# Fake6523.net
KiCad netlist of a schematic drawn in EAGLE
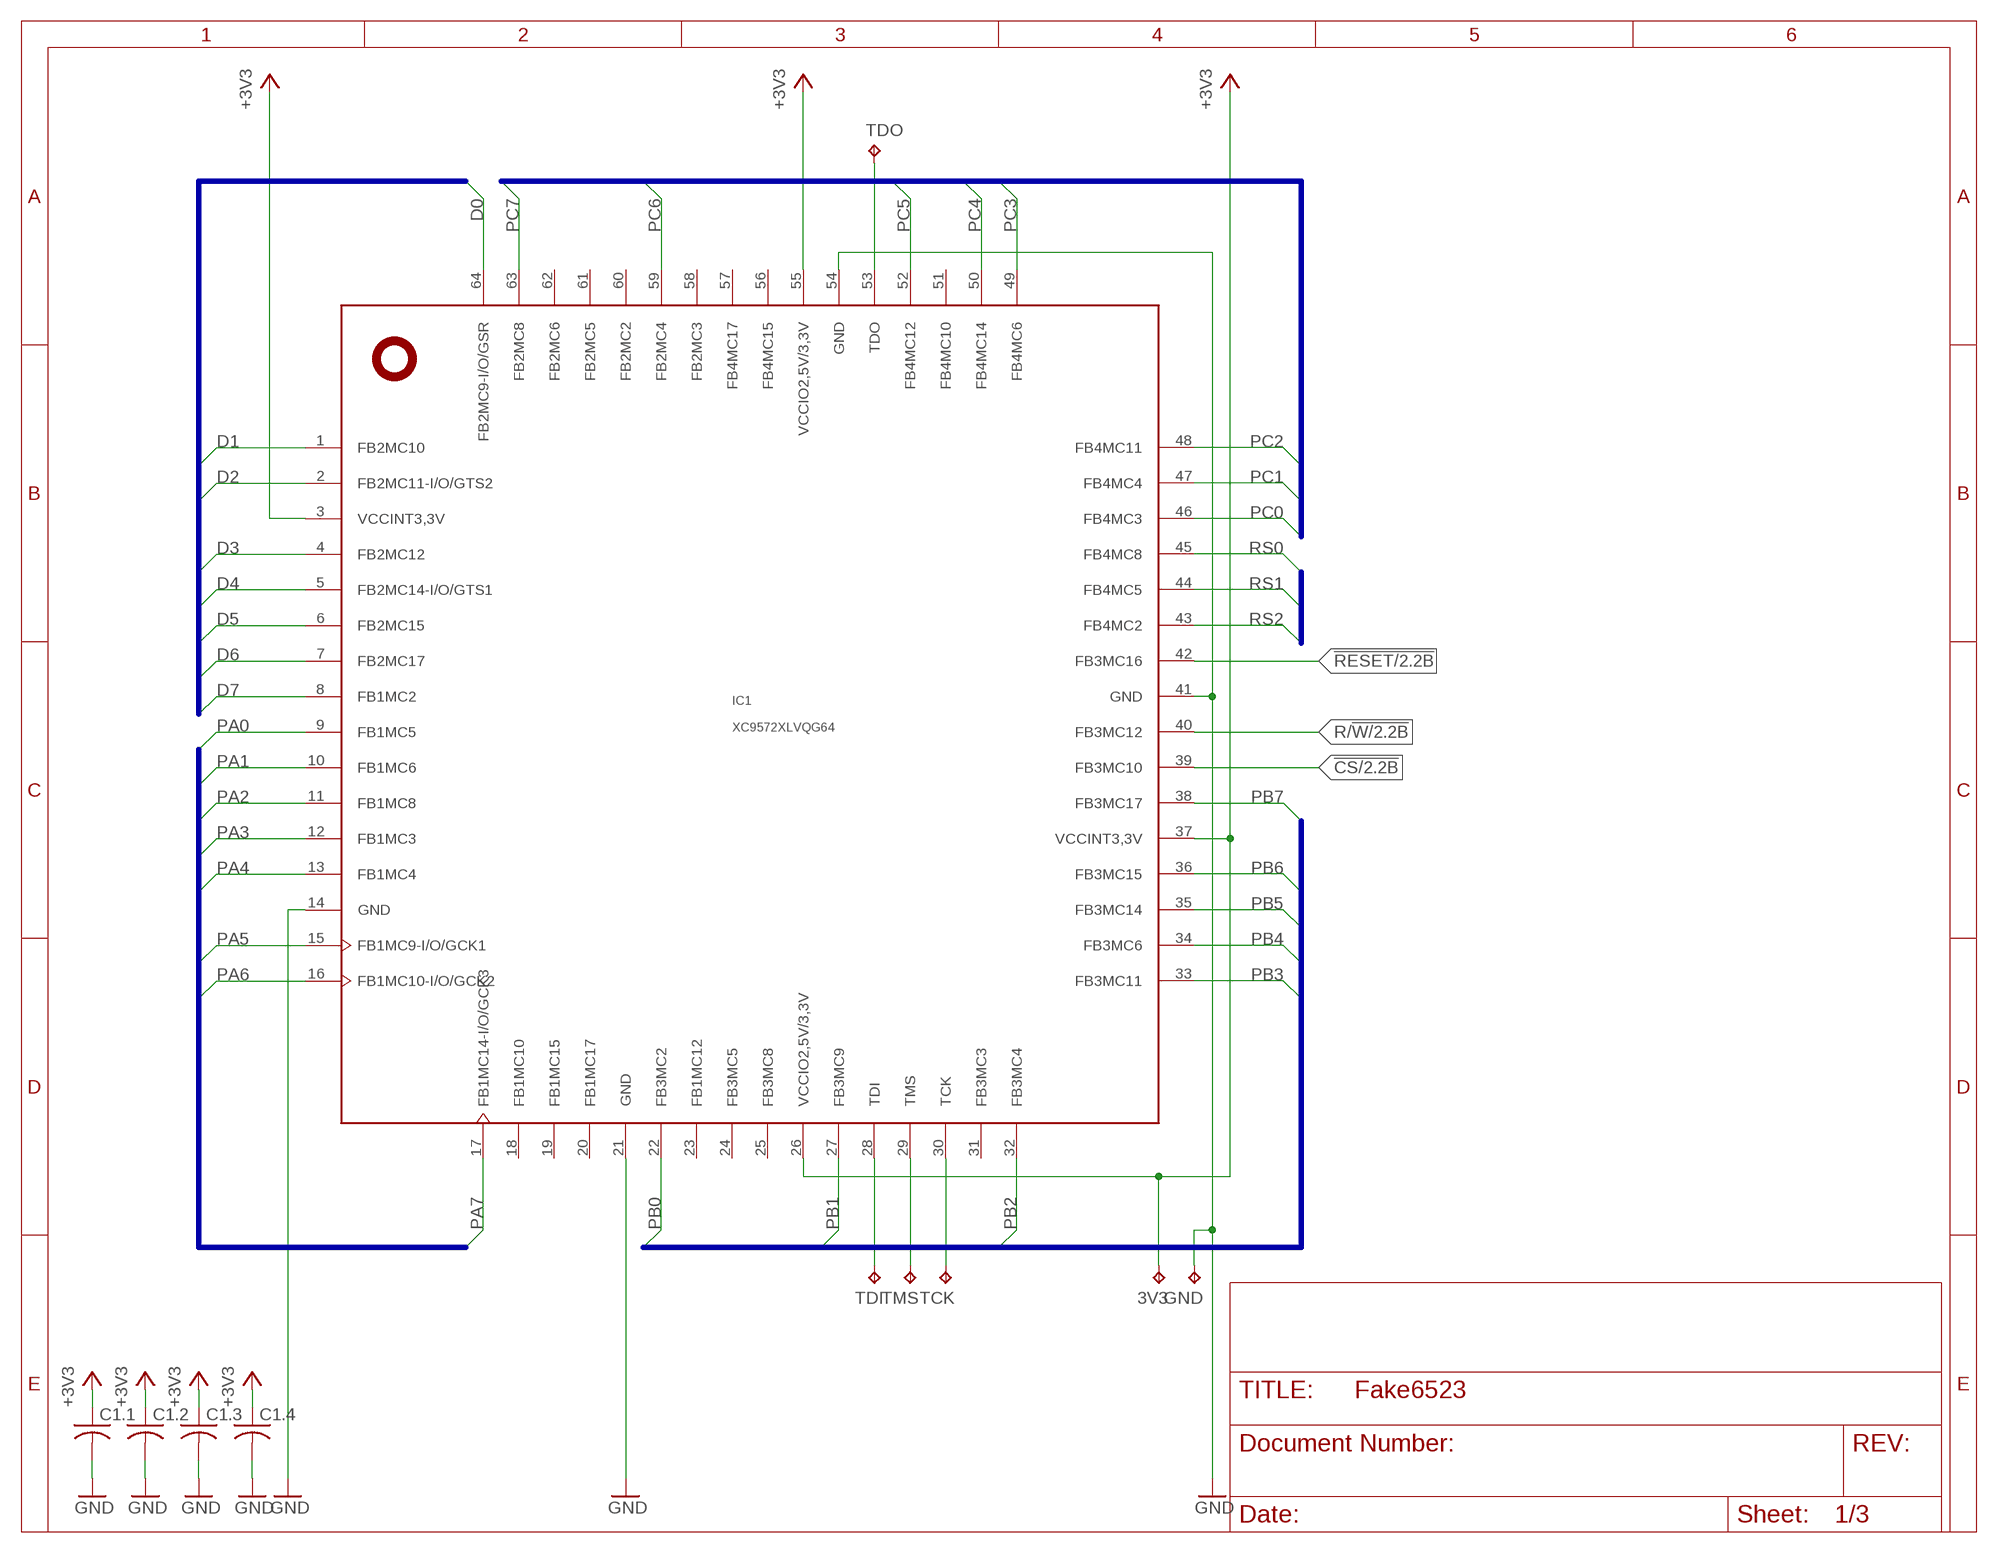
[diagram p0: schematic, sheet 1]
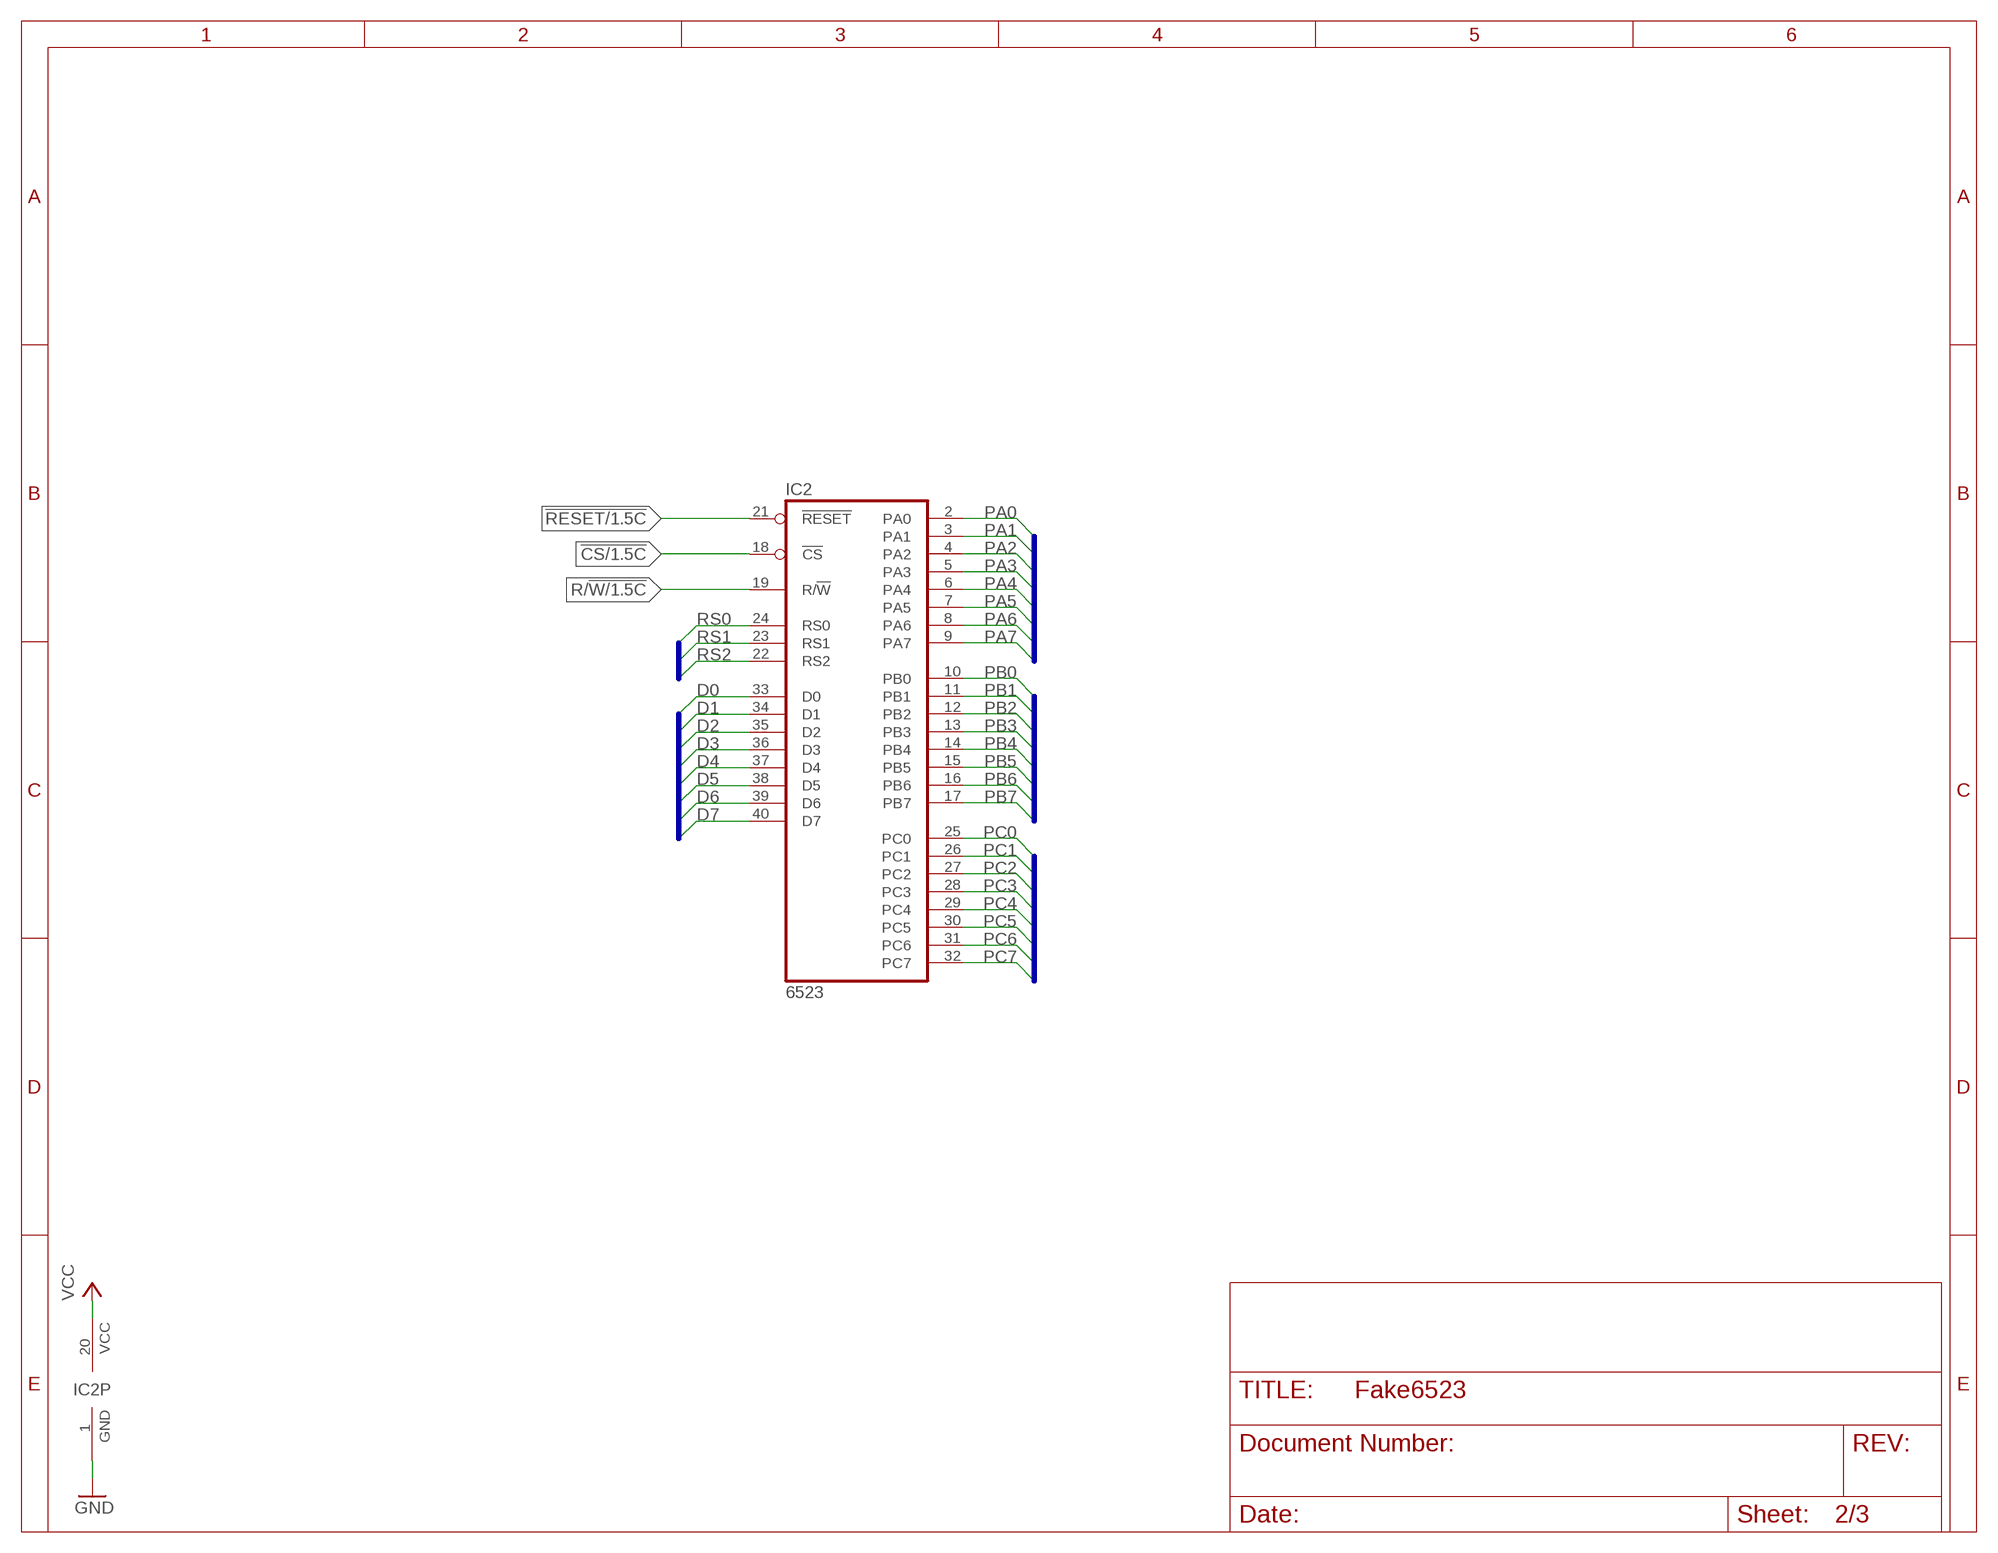
[diagram p1: schematic, sheet 2]
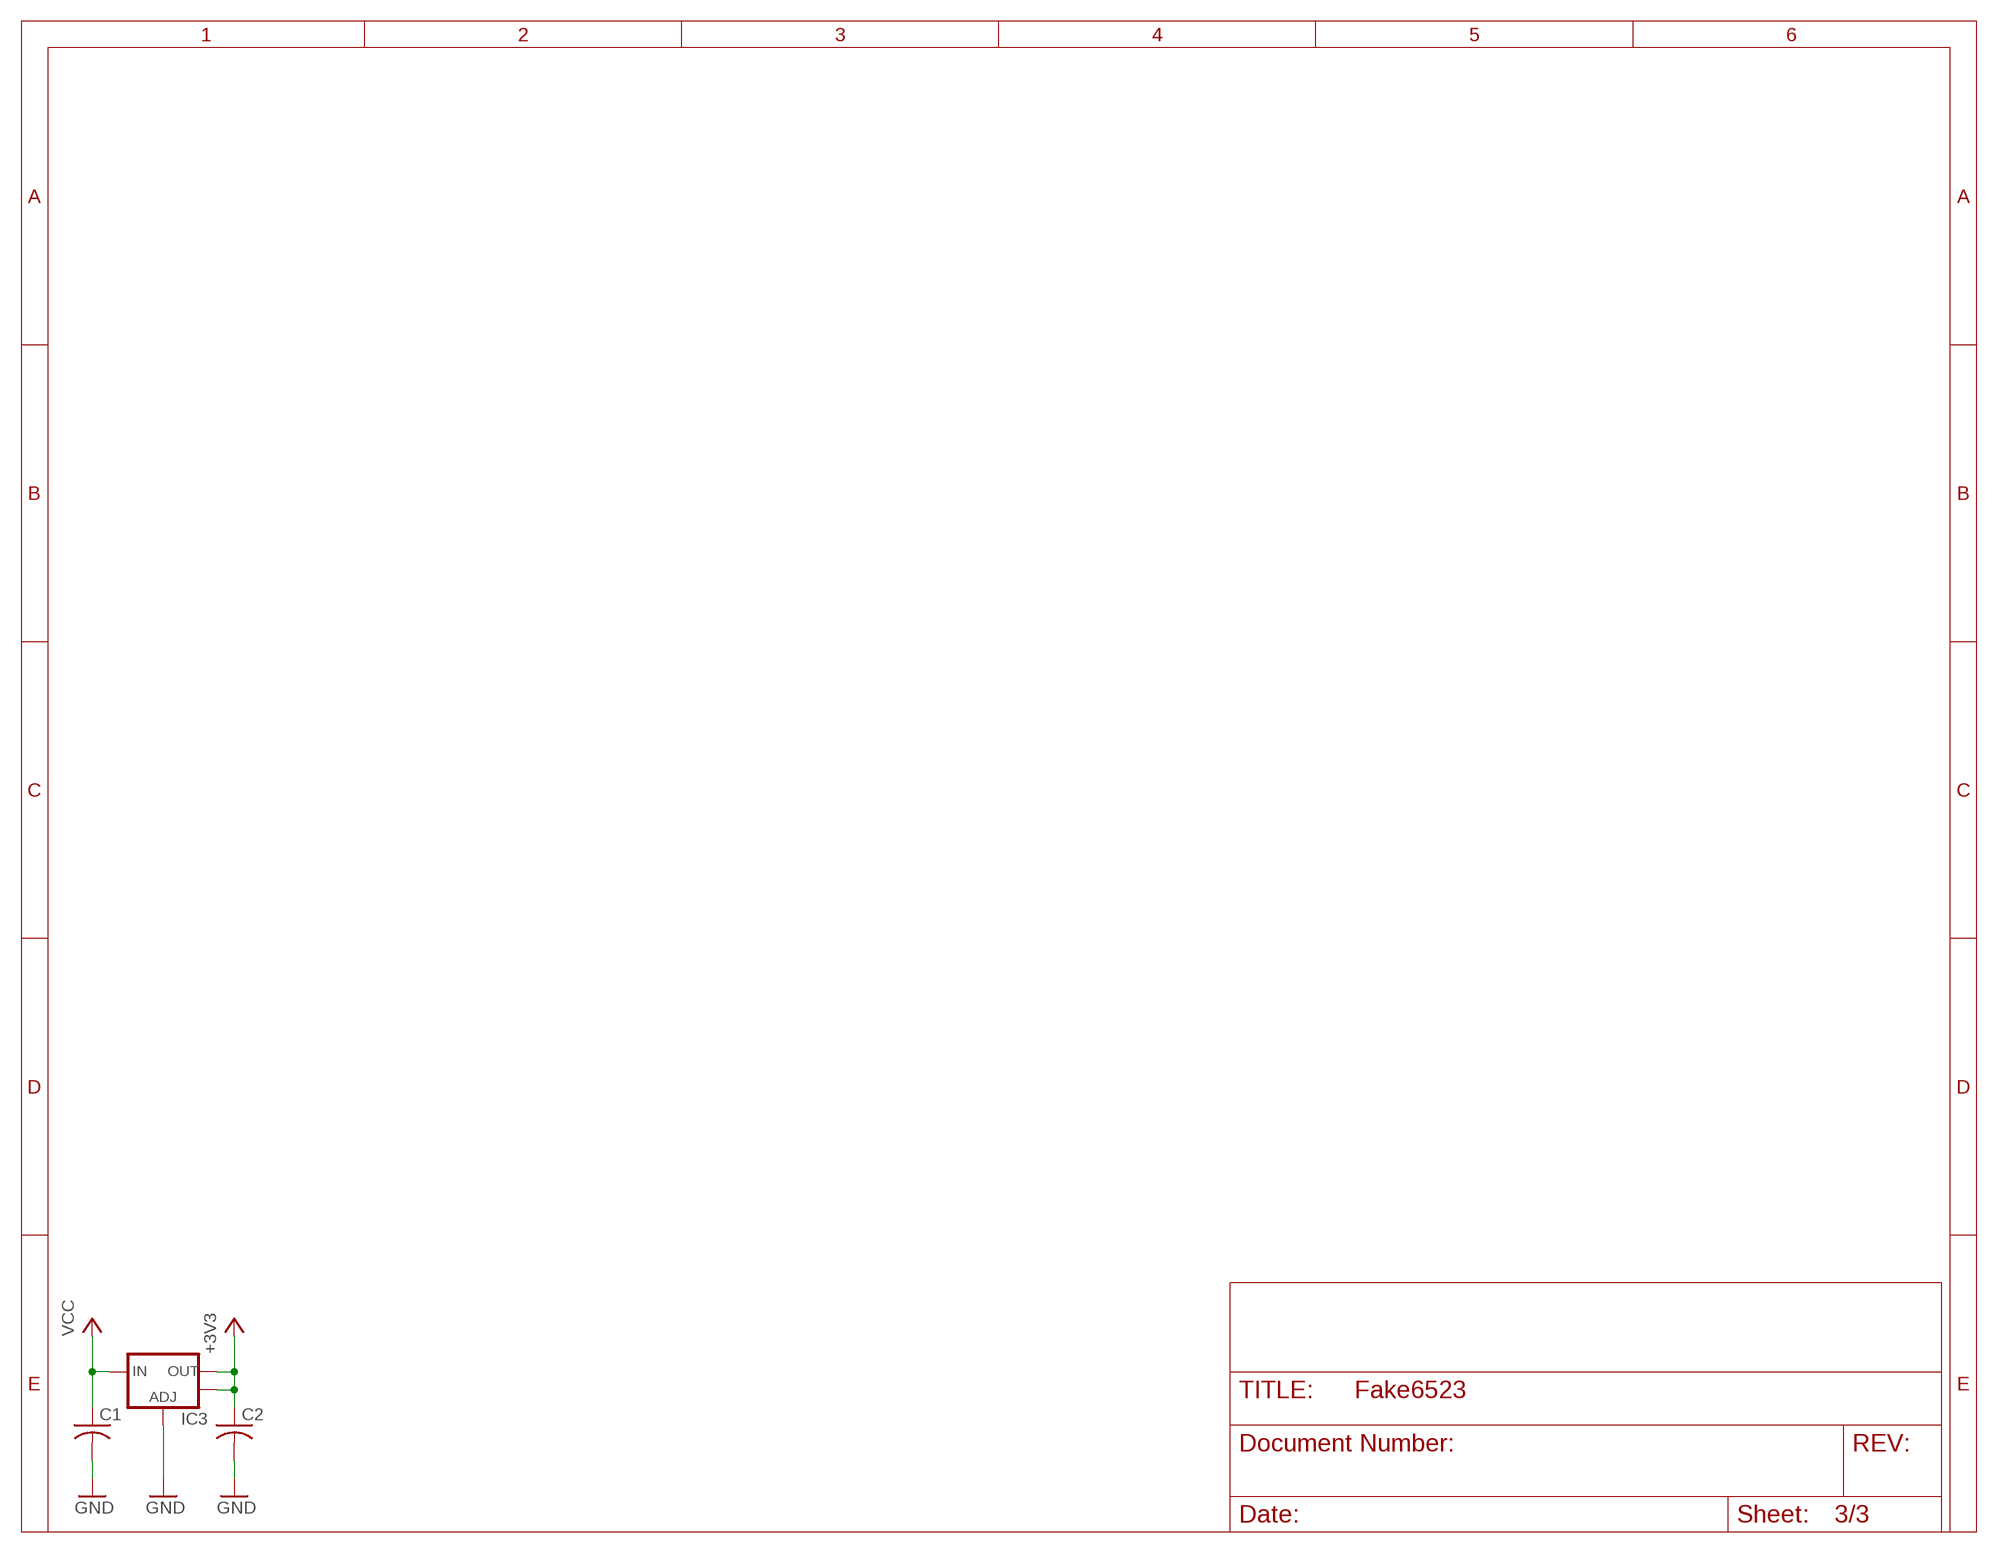
[diagram p2: schematic, sheet 3]

(export (version "E")
  (design (tool "Eeschema 10.0.6"))
  (components
    (comp (ref "3V3")
      (value "TPTP08R")
      (footprint "eagle-import:TP08R")
      (libsource (lib "eagle-import") (part "TPTP08R"))
    )
    (comp (ref "C1.1")
      (value "C-USC0402")
      (footprint "eagle-import:C0402")
      (libsource (lib "eagle-import") (part "C-USC0402"))
    )
    (comp (ref "C1.2")
      (value "C-USC0402")
      (footprint "eagle-import:C0402")
      (libsource (lib "eagle-import") (part "C-USC0402"))
    )
    (comp (ref "C1.3")
      (value "C-USC0402")
      (footprint "eagle-import:C0402")
      (libsource (lib "eagle-import") (part "C-USC0402"))
    )
    (comp (ref "C1.4")
      (value "C-USC0402")
      (footprint "eagle-import:C0402")
      (libsource (lib "eagle-import") (part "C-USC0402"))
    )
    (comp (ref "GND")
      (value "TPTP08R")
      (footprint "eagle-import:TP08R")
      (libsource (lib "eagle-import") (part "TPTP08R"))
    )
    (comp (ref "IC1")
      (value "XC9572XLVQG64")
      (footprint "eagle-import:VQFP64")
      (libsource (lib "eagle-import") (part "XC9572XLVQG64"))
    )
    (comp (ref "TCK")
      (value "TPTP08R")
      (footprint "eagle-import:TP08R")
      (libsource (lib "eagle-import") (part "TPTP08R"))
    )
    (comp (ref "TDI")
      (value "TPTP08R")
      (footprint "eagle-import:TP08R")
      (libsource (lib "eagle-import") (part "TPTP08R"))
    )
    (comp (ref "TDO")
      (value "TPTP08R")
      (footprint "eagle-import:TP08R")
      (libsource (lib "eagle-import") (part "TPTP08R"))
    )
    (comp (ref "TMS")
      (value "TPTP08R")
      (footprint "eagle-import:TP08R")
      (libsource (lib "eagle-import") (part "TPTP08R"))
    )
    (comp (ref "IC2")
      (value "6523")
      (footprint "eagle-import:DIL40-ROUNDPAD")
      (libsource (lib "eagle-import") (part "6523-R"))
    )
    (comp (ref "C1")
      (value "C-USC0805")
      (footprint "eagle-import:C0805")
      (libsource (lib "eagle-import") (part "C-USC0805"))
    )
    (comp (ref "C2")
      (value "C-USC0805")
      (footprint "eagle-import:C0805")
      (libsource (lib "eagle-import") (part "C-USC0805"))
    )
    (comp (ref "IC3")
      (value "V_REG_LM1117SOT223")
      (footprint "eagle-import:SOT223")
      (libsource (lib "eagle-import") (part "V_REG_LM1117SOT223"))
    )
  )
  (nets
    (net (code "1") (name "+3V3") (class "Default")
      (node (ref "3V3") (pin "TP") (pinfunction "TP_TP") (pintype "input"))
      (node (ref "C1.1") (pin "1") (pinfunction "1_1") (pintype "passive"))
      (node (ref "C1.2") (pin "1") (pinfunction "1_1") (pintype "passive"))
      (node (ref "C1.3") (pin "1") (pinfunction "1_1") (pintype "passive"))
      (node (ref "C1.4") (pin "1") (pinfunction "1_1") (pintype "passive"))
      (node (ref "C2") (pin "1") (pinfunction "1_1") (pintype "passive"))
      (node (ref "IC1") (pin "26") (pinfunction "VCCIO2,5V/3,3V_26") (pintype "power_in"))
      (node (ref "IC1") (pin "3") (pinfunction "VCCINT3,3V_3") (pintype "power_in"))
      (node (ref "IC1") (pin "37") (pinfunction "VCCINT3,3V_37") (pintype "power_in"))
      (node (ref "IC1") (pin "55") (pinfunction "VCCIO2,5V/3,3V_55") (pintype "power_in"))
      (node (ref "IC3") (pin "2") (pinfunction "OUT_2") (pintype "output"))
      (node (ref "IC3") (pin "4") (pinfunction "OUT_4") (pintype "output"))
    )
    (net (code "2") (name "D0") (class "Default")
      (node (ref "IC1") (pin "64") (pinfunction "FB2MC9-I/O/GSR_64") (pintype "bidirectional"))
      (node (ref "IC2") (pin "33") (pinfunction "D0_33") (pintype "bidirectional"))
    )
    (net (code "3") (name "D1") (class "Default")
      (node (ref "IC1") (pin "1") (pinfunction "FB2MC10_1") (pintype "bidirectional"))
      (node (ref "IC2") (pin "34") (pinfunction "D1_34") (pintype "bidirectional"))
    )
    (net (code "4") (name "D2") (class "Default")
      (node (ref "IC1") (pin "2") (pinfunction "FB2MC11-I/O/GTS2_2") (pintype "bidirectional"))
      (node (ref "IC2") (pin "35") (pinfunction "D2_35") (pintype "bidirectional"))
    )
    (net (code "5") (name "D3") (class "Default")
      (node (ref "IC1") (pin "4") (pinfunction "FB2MC12_4") (pintype "bidirectional"))
      (node (ref "IC2") (pin "36") (pinfunction "D3_36") (pintype "bidirectional"))
    )
    (net (code "6") (name "D4") (class "Default")
      (node (ref "IC1") (pin "5") (pinfunction "FB2MC14-I/O/GTS1_5") (pintype "bidirectional"))
      (node (ref "IC2") (pin "37") (pinfunction "D4_37") (pintype "bidirectional"))
    )
    (net (code "7") (name "D5") (class "Default")
      (node (ref "IC1") (pin "6") (pinfunction "FB2MC15_6") (pintype "bidirectional"))
      (node (ref "IC2") (pin "38") (pinfunction "D5_38") (pintype "bidirectional"))
    )
    (net (code "8") (name "D6") (class "Default")
      (node (ref "IC1") (pin "7") (pinfunction "FB2MC17_7") (pintype "bidirectional"))
      (node (ref "IC2") (pin "39") (pinfunction "D6_39") (pintype "bidirectional"))
    )
    (net (code "9") (name "D7") (class "Default")
      (node (ref "IC1") (pin "8") (pinfunction "FB1MC2_8") (pintype "bidirectional"))
      (node (ref "IC2") (pin "40") (pinfunction "D7_40") (pintype "bidirectional"))
    )
    (net (code "10") (name "GND") (class "Default")
      (node (ref "C1") (pin "2") (pinfunction "2_2") (pintype "passive"))
      (node (ref "C1.1") (pin "2") (pinfunction "2_2") (pintype "passive"))
      (node (ref "C1.2") (pin "2") (pinfunction "2_2") (pintype "passive"))
      (node (ref "C1.3") (pin "2") (pinfunction "2_2") (pintype "passive"))
      (node (ref "C1.4") (pin "2") (pinfunction "2_2") (pintype "passive"))
      (node (ref "C2") (pin "2") (pinfunction "2_2") (pintype "passive"))
      (node (ref "GND") (pin "TP") (pinfunction "TP_TP") (pintype "input"))
      (node (ref "IC1") (pin "14") (pinfunction "GND_14") (pintype "power_in"))
      (node (ref "IC1") (pin "21") (pinfunction "GND_21") (pintype "power_in"))
      (node (ref "IC1") (pin "41") (pinfunction "GND_41") (pintype "power_in"))
      (node (ref "IC1") (pin "54") (pinfunction "GND_54") (pintype "power_in"))
      (node (ref "IC2") (pin "1") (pinfunction "GND_1") (pintype "power_in"))
      (node (ref "IC3") (pin "1") (pinfunction "ADJ_1") (pintype "input"))
    )
    (net (code "11") (name "Net-(IC1-TCK)") (class "Default")
      (node (ref "IC1") (pin "30") (pinfunction "TCK_30") (pintype "bidirectional"))
      (node (ref "TCK") (pin "TP") (pinfunction "TP_TP") (pintype "input"))
    )
    (net (code "12") (name "Net-(IC1-TDI)") (class "Default")
      (node (ref "IC1") (pin "28") (pinfunction "TDI_28") (pintype "bidirectional"))
      (node (ref "TDI") (pin "TP") (pinfunction "TP_TP") (pintype "input"))
    )
    (net (code "13") (name "Net-(IC1-TDO)") (class "Default")
      (node (ref "IC1") (pin "53") (pinfunction "TDO_53") (pintype "bidirectional"))
      (node (ref "TDO") (pin "TP") (pinfunction "TP_TP") (pintype "input"))
    )
    (net (code "14") (name "Net-(IC1-TMS)") (class "Default")
      (node (ref "IC1") (pin "29") (pinfunction "TMS_29") (pintype "bidirectional"))
      (node (ref "TMS") (pin "TP") (pinfunction "TP_TP") (pintype "input"))
    )
    (net (code "15") (name "PA0") (class "Default")
      (node (ref "IC1") (pin "9") (pinfunction "FB1MC5_9") (pintype "bidirectional"))
      (node (ref "IC2") (pin "2") (pinfunction "PA0_2") (pintype "bidirectional"))
    )
    (net (code "16") (name "PA1") (class "Default")
      (node (ref "IC1") (pin "10") (pinfunction "FB1MC6_10") (pintype "bidirectional"))
      (node (ref "IC2") (pin "3") (pinfunction "PA1_3") (pintype "bidirectional"))
    )
    (net (code "17") (name "PA2") (class "Default")
      (node (ref "IC1") (pin "11") (pinfunction "FB1MC8_11") (pintype "bidirectional"))
      (node (ref "IC2") (pin "4") (pinfunction "PA2_4") (pintype "bidirectional"))
    )
    (net (code "18") (name "PA3") (class "Default")
      (node (ref "IC1") (pin "12") (pinfunction "FB1MC3_12") (pintype "bidirectional"))
      (node (ref "IC2") (pin "5") (pinfunction "PA3_5") (pintype "bidirectional"))
    )
    (net (code "19") (name "PA4") (class "Default")
      (node (ref "IC1") (pin "13") (pinfunction "FB1MC4_13") (pintype "bidirectional"))
      (node (ref "IC2") (pin "6") (pinfunction "PA4_6") (pintype "bidirectional"))
    )
    (net (code "20") (name "PA5") (class "Default")
      (node (ref "IC1") (pin "15") (pinfunction "FB1MC9-I/O/GCK1_15") (pintype "bidirectional"))
      (node (ref "IC2") (pin "7") (pinfunction "PA5_7") (pintype "bidirectional"))
    )
    (net (code "21") (name "PA6") (class "Default")
      (node (ref "IC1") (pin "16") (pinfunction "FB1MC10-I/O/GCK2_16") (pintype "bidirectional"))
      (node (ref "IC2") (pin "8") (pinfunction "PA6_8") (pintype "bidirectional"))
    )
    (net (code "22") (name "PA7") (class "Default")
      (node (ref "IC1") (pin "17") (pinfunction "FB1MC14-I/O/GCK3_17") (pintype "bidirectional"))
      (node (ref "IC2") (pin "9") (pinfunction "PA7_9") (pintype "bidirectional"))
    )
    (net (code "23") (name "PB0") (class "Default")
      (node (ref "IC1") (pin "22") (pinfunction "FB3MC2_22") (pintype "bidirectional"))
      (node (ref "IC2") (pin "10") (pinfunction "PB0_10") (pintype "bidirectional"))
    )
    (net (code "24") (name "PB1") (class "Default")
      (node (ref "IC1") (pin "27") (pinfunction "FB3MC9_27") (pintype "bidirectional"))
      (node (ref "IC2") (pin "11") (pinfunction "PB1_11") (pintype "bidirectional"))
    )
    (net (code "25") (name "PB2") (class "Default")
      (node (ref "IC1") (pin "32") (pinfunction "FB3MC4_32") (pintype "bidirectional"))
      (node (ref "IC2") (pin "12") (pinfunction "PB2_12") (pintype "bidirectional"))
    )
    (net (code "26") (name "PB3") (class "Default")
      (node (ref "IC1") (pin "33") (pinfunction "FB3MC11_33") (pintype "bidirectional"))
      (node (ref "IC2") (pin "13") (pinfunction "PB3_13") (pintype "bidirectional"))
    )
    (net (code "27") (name "PB4") (class "Default")
      (node (ref "IC1") (pin "34") (pinfunction "FB3MC6_34") (pintype "bidirectional"))
      (node (ref "IC2") (pin "14") (pinfunction "PB4_14") (pintype "bidirectional"))
    )
    (net (code "28") (name "PB5") (class "Default")
      (node (ref "IC1") (pin "35") (pinfunction "FB3MC14_35") (pintype "bidirectional"))
      (node (ref "IC2") (pin "15") (pinfunction "PB5_15") (pintype "bidirectional"))
    )
    (net (code "29") (name "PB6") (class "Default")
      (node (ref "IC1") (pin "36") (pinfunction "FB3MC15_36") (pintype "bidirectional"))
      (node (ref "IC2") (pin "16") (pinfunction "PB6_16") (pintype "bidirectional"))
    )
    (net (code "30") (name "PB7") (class "Default")
      (node (ref "IC1") (pin "38") (pinfunction "FB3MC17_38") (pintype "bidirectional"))
      (node (ref "IC2") (pin "17") (pinfunction "PB7_17") (pintype "bidirectional"))
    )
    (net (code "31") (name "PC0") (class "Default")
      (node (ref "IC1") (pin "46") (pinfunction "FB4MC3_46") (pintype "bidirectional"))
      (node (ref "IC2") (pin "25") (pinfunction "PC0_25") (pintype "bidirectional"))
    )
    (net (code "32") (name "PC1") (class "Default")
      (node (ref "IC1") (pin "47") (pinfunction "FB4MC4_47") (pintype "bidirectional"))
      (node (ref "IC2") (pin "26") (pinfunction "PC1_26") (pintype "bidirectional"))
    )
    (net (code "33") (name "PC2") (class "Default")
      (node (ref "IC1") (pin "48") (pinfunction "FB4MC11_48") (pintype "bidirectional"))
      (node (ref "IC2") (pin "27") (pinfunction "PC2_27") (pintype "bidirectional"))
    )
    (net (code "34") (name "PC3") (class "Default")
      (node (ref "IC1") (pin "49") (pinfunction "FB4MC6_49") (pintype "bidirectional"))
      (node (ref "IC2") (pin "28") (pinfunction "PC3_28") (pintype "bidirectional"))
    )
    (net (code "35") (name "PC4") (class "Default")
      (node (ref "IC1") (pin "50") (pinfunction "FB4MC14_50") (pintype "bidirectional"))
      (node (ref "IC2") (pin "29") (pinfunction "PC4_29") (pintype "bidirectional"))
    )
    (net (code "36") (name "PC5") (class "Default")
      (node (ref "IC1") (pin "52") (pinfunction "FB4MC12_52") (pintype "bidirectional"))
      (node (ref "IC2") (pin "30") (pinfunction "PC5_30") (pintype "bidirectional"))
    )
    (net (code "37") (name "PC6") (class "Default")
      (node (ref "IC1") (pin "59") (pinfunction "FB2MC4_59") (pintype "bidirectional"))
      (node (ref "IC2") (pin "31") (pinfunction "PC6_31") (pintype "bidirectional"))
    )
    (net (code "38") (name "PC7") (class "Default")
      (node (ref "IC1") (pin "63") (pinfunction "FB2MC8_63") (pintype "bidirectional"))
      (node (ref "IC2") (pin "32") (pinfunction "PC7_32") (pintype "bidirectional"))
    )
    (net (code "39") (name "RS0") (class "Default")
      (node (ref "IC1") (pin "45") (pinfunction "FB4MC8_45") (pintype "bidirectional"))
      (node (ref "IC2") (pin "24") (pinfunction "RS0_24") (pintype "input"))
    )
    (net (code "40") (name "RS1") (class "Default")
      (node (ref "IC1") (pin "44") (pinfunction "FB4MC5_44") (pintype "bidirectional"))
      (node (ref "IC2") (pin "23") (pinfunction "RS1_23") (pintype "input"))
    )
    (net (code "41") (name "RS2") (class "Default")
      (node (ref "IC1") (pin "43") (pinfunction "FB4MC2_43") (pintype "bidirectional"))
      (node (ref "IC2") (pin "22") (pinfunction "RS2_22") (pintype "input"))
    )
    (net (code "42") (name "R{slash}~{W}") (class "Default")
      (node (ref "IC1") (pin "40") (pinfunction "FB3MC12_40") (pintype "bidirectional"))
      (node (ref "IC2") (pin "19") (pinfunction "R/~{W}_19") (pintype "input"))
    )
    (net (code "43") (name "VCC") (class "Default")
      (node (ref "C1") (pin "1") (pinfunction "1_1") (pintype "passive"))
      (node (ref "IC2") (pin "20") (pinfunction "VCC_20") (pintype "power_in"))
      (node (ref "IC3") (pin "3") (pinfunction "IN_3") (pintype "input"))
    )
    (net (code "44") (name "unconnected-(IC1-FB1MC10-Pad18)") (class "Default")
      (node (ref "IC1") (pin "18") (pinfunction "FB1MC10_18") (pintype "bidirectional"))
    )
    (net (code "45") (name "unconnected-(IC1-FB1MC12-Pad23)") (class "Default")
      (node (ref "IC1") (pin "23") (pinfunction "FB1MC12_23") (pintype "bidirectional"))
    )
    (net (code "46") (name "unconnected-(IC1-FB1MC15-Pad19)") (class "Default")
      (node (ref "IC1") (pin "19") (pinfunction "FB1MC15_19") (pintype "bidirectional"))
    )
    (net (code "47") (name "unconnected-(IC1-FB1MC17-Pad20)") (class "Default")
      (node (ref "IC1") (pin "20") (pinfunction "FB1MC17_20") (pintype "bidirectional"))
    )
    (net (code "48") (name "unconnected-(IC1-FB2MC2-Pad60)") (class "Default")
      (node (ref "IC1") (pin "60") (pinfunction "FB2MC2_60") (pintype "bidirectional"))
    )
    (net (code "49") (name "unconnected-(IC1-FB2MC3-Pad58)") (class "Default")
      (node (ref "IC1") (pin "58") (pinfunction "FB2MC3_58") (pintype "bidirectional"))
    )
    (net (code "50") (name "unconnected-(IC1-FB2MC5-Pad61)") (class "Default")
      (node (ref "IC1") (pin "61") (pinfunction "FB2MC5_61") (pintype "bidirectional"))
    )
    (net (code "51") (name "unconnected-(IC1-FB2MC6-Pad62)") (class "Default")
      (node (ref "IC1") (pin "62") (pinfunction "FB2MC6_62") (pintype "bidirectional"))
    )
    (net (code "52") (name "unconnected-(IC1-FB3MC3-Pad31)") (class "Default")
      (node (ref "IC1") (pin "31") (pinfunction "FB3MC3_31") (pintype "bidirectional"))
    )
    (net (code "53") (name "unconnected-(IC1-FB3MC5-Pad24)") (class "Default")
      (node (ref "IC1") (pin "24") (pinfunction "FB3MC5_24") (pintype "bidirectional"))
    )
    (net (code "54") (name "unconnected-(IC1-FB3MC8-Pad25)") (class "Default")
      (node (ref "IC1") (pin "25") (pinfunction "FB3MC8_25") (pintype "bidirectional"))
    )
    (net (code "55") (name "unconnected-(IC1-FB4MC10-Pad51)") (class "Default")
      (node (ref "IC1") (pin "51") (pinfunction "FB4MC10_51") (pintype "bidirectional"))
    )
    (net (code "56") (name "unconnected-(IC1-FB4MC15-Pad56)") (class "Default")
      (node (ref "IC1") (pin "56") (pinfunction "FB4MC15_56") (pintype "bidirectional"))
    )
    (net (code "57") (name "unconnected-(IC1-FB4MC17-Pad57)") (class "Default")
      (node (ref "IC1") (pin "57") (pinfunction "FB4MC17_57") (pintype "bidirectional"))
    )
    (net (code "58") (name "~{CS}") (class "Default")
      (node (ref "IC1") (pin "39") (pinfunction "FB3MC10_39") (pintype "bidirectional"))
      (node (ref "IC2") (pin "18") (pinfunction "~{CS}_18") (pintype "input"))
    )
    (net (code "59") (name "~{RESET}") (class "Default")
      (node (ref "IC1") (pin "42") (pinfunction "FB3MC16_42") (pintype "bidirectional"))
      (node (ref "IC2") (pin "21") (pinfunction "~{RESET}_21") (pintype "input"))
    )
  )
)
